# ETHERNET.net
KiCad netlist of a schematic drawn in Altium Designer
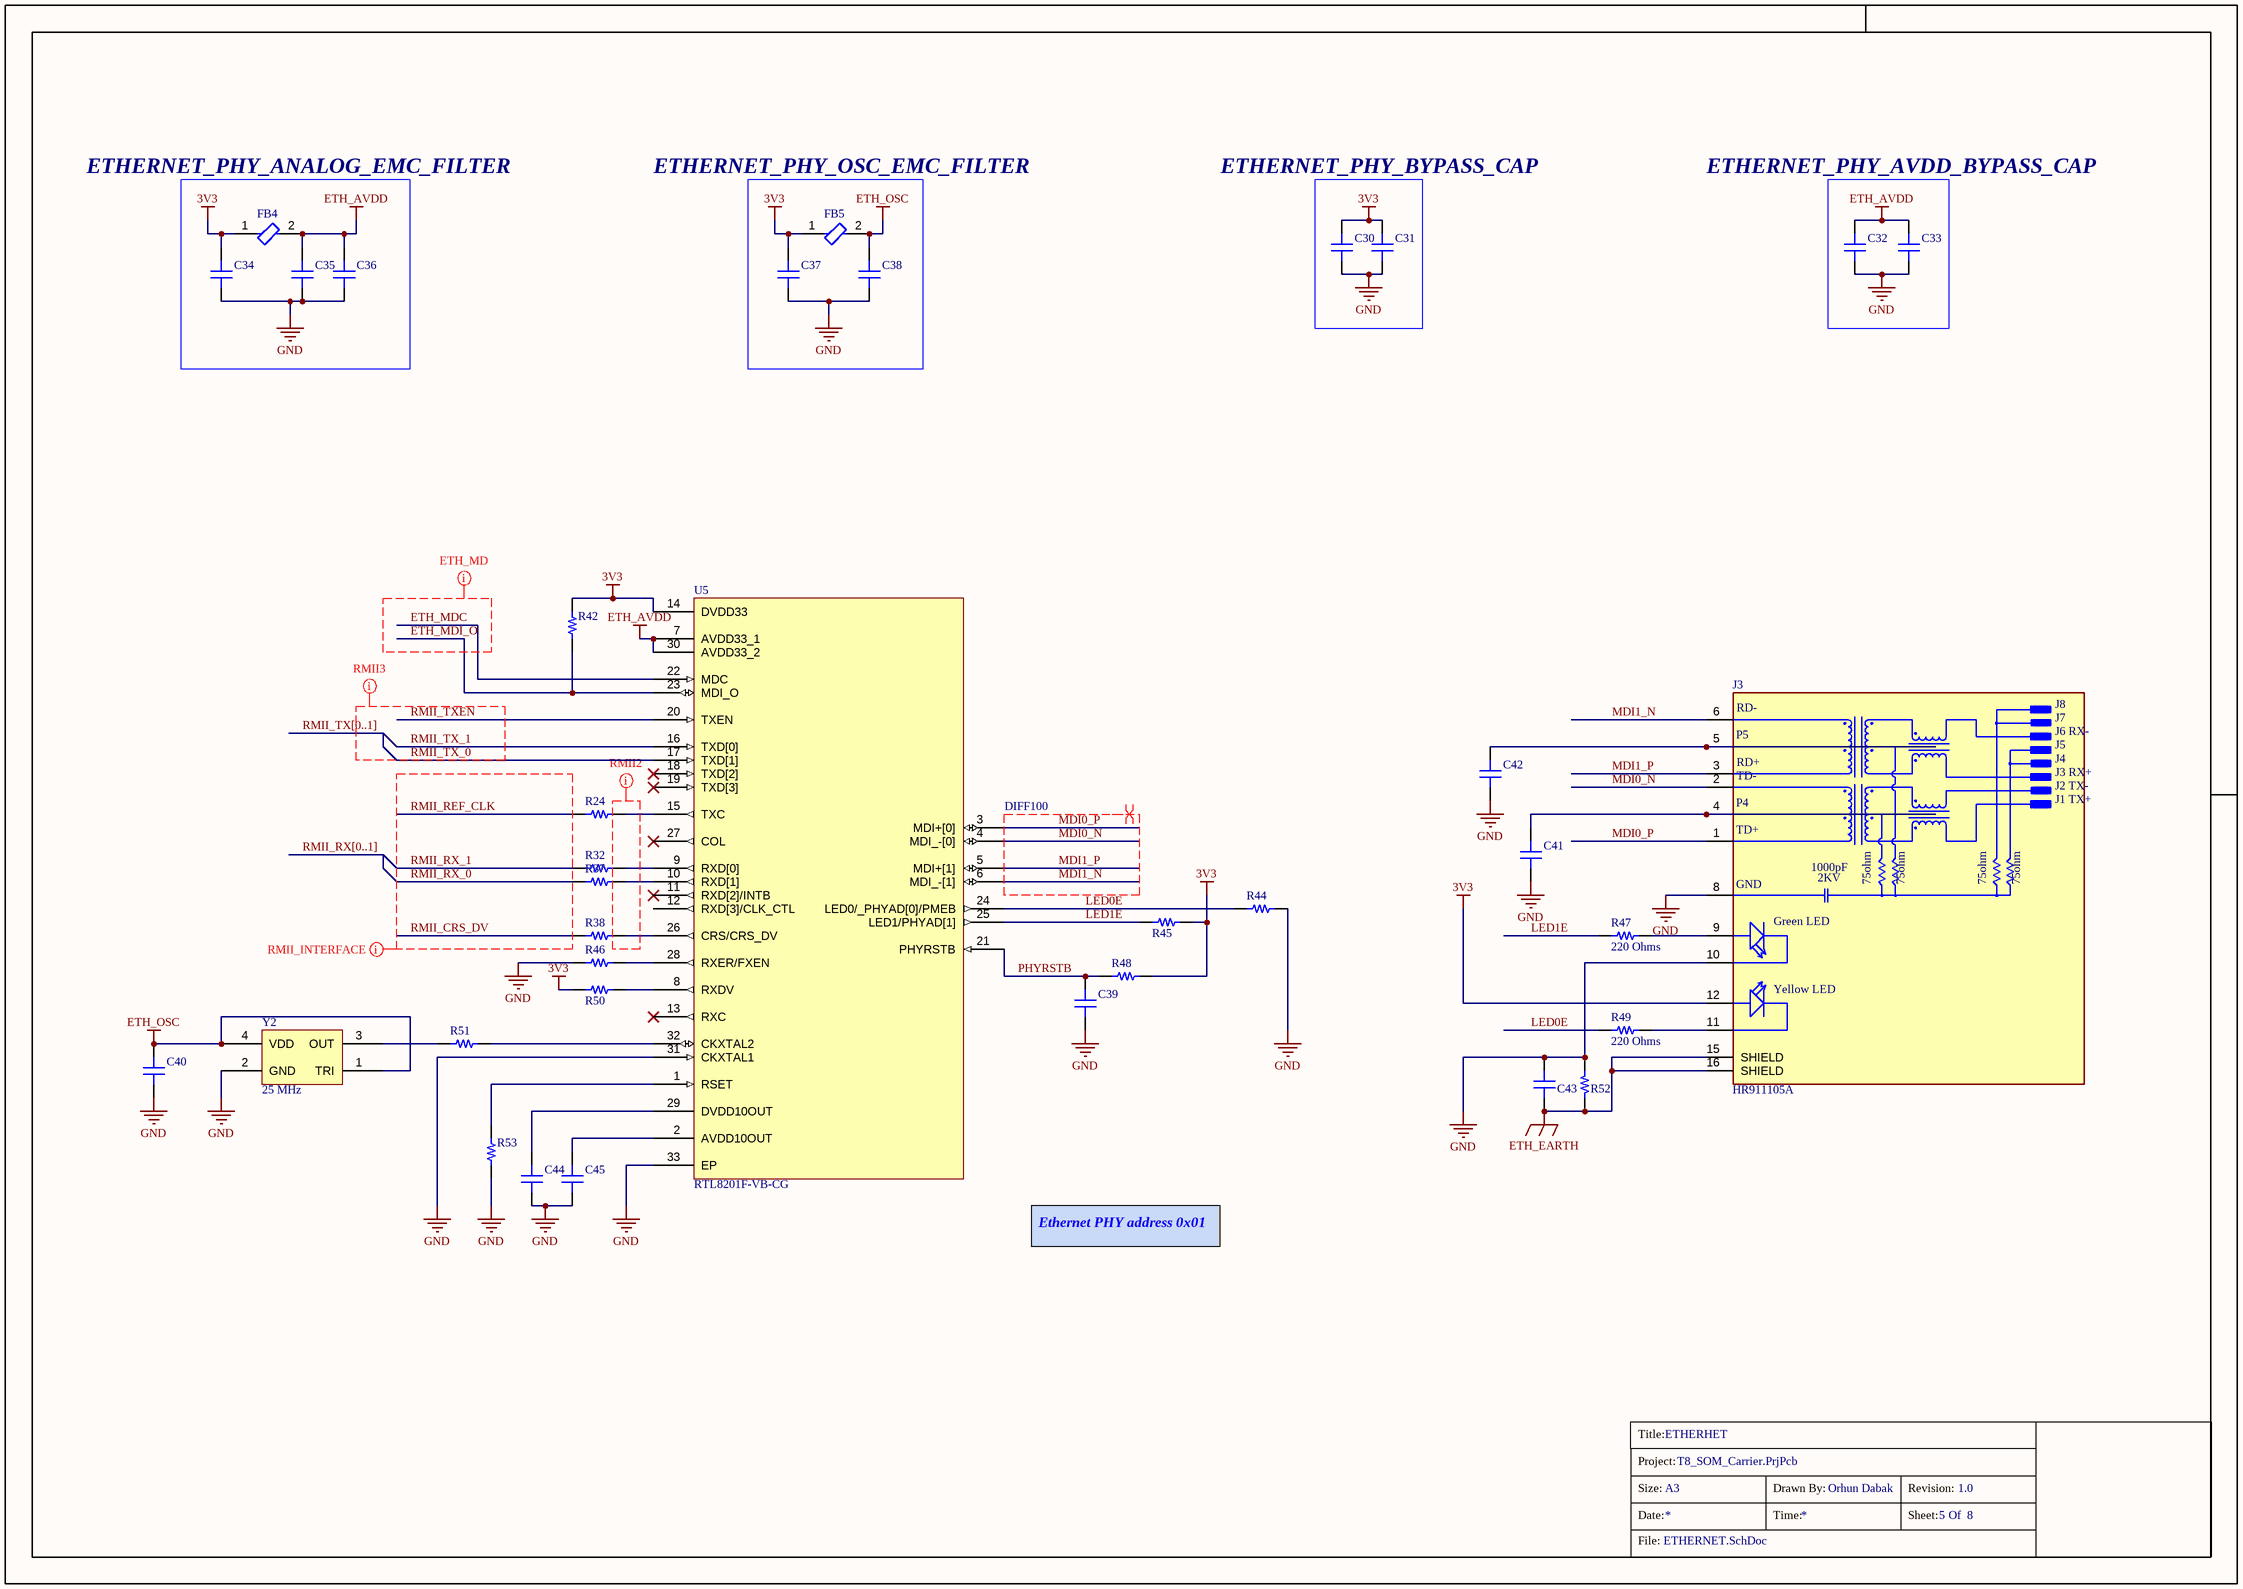
[diagram p0: ETHERNET.SchDoc]

(export (version "E")
  (design (tool "Eeschema 10.0.6"))
  (components
    (comp (ref "C30")
      (value "0.1 µF")
      (footprint "CAP 0402_1005")
      (description "CAP CER 0.1UF 10V X7R 0402")
      (fields (field (name "PART NUMBER") "CC0402KRX7R6BB104") (field (name "MANUFACTURER") "Yageo"))
      (libsource (lib "Celestial Altium Library - altium_library") (part "Capacitor"))
    )
    (comp (ref "C31")
      (value "2.2 µF")
      (footprint "CAP 0402_1005")
      (description "CAP CER 2.2UF 10V X5R 0402")
      (fields (field (name "PART NUMBER") "C0402C225M8PAC7867") (field (name "MANUFACTURER") "KEMET"))
      (libsource (lib "Celestial Altium Library - altium_library") (part "Capacitor"))
    )
    (comp (ref "C32")
      (value "0.1 µF")
      (footprint "CAP 0402_1005")
      (description "CAP CER 0.1UF 10V X7R 0402")
      (fields (field (name "PART NUMBER") "CC0402KRX7R6BB104") (field (name "MANUFACTURER") "Yageo"))
      (libsource (lib "Celestial Altium Library - altium_library") (part "Capacitor"))
    )
    (comp (ref "C33")
      (value "0.1 µF")
      (footprint "CAP 0402_1005")
      (description "CAP CER 0.1UF 10V X7R 0402")
      (fields (field (name "PART NUMBER") "CC0402KRX7R6BB104") (field (name "MANUFACTURER") "Yageo"))
      (libsource (lib "Celestial Altium Library - altium_library") (part "Capacitor"))
    )
    (comp (ref "C34")
      (value "0.1 µF")
      (footprint "CAP 0402_1005")
      (description "CAP CER 0.1UF 10V X7R 0402")
      (fields (field (name "PART NUMBER") "CC0402KRX7R6BB104") (field (name "MANUFACTURER") "Yageo"))
      (libsource (lib "Celestial Altium Library - altium_library") (part "Capacitor"))
    )
    (comp (ref "C35")
      (value "0.1 µF")
      (footprint "CAP 0402_1005")
      (description "CAP CER 0.1UF 10V X7R 0402")
      (fields (field (name "PART NUMBER") "CC0402KRX7R6BB104") (field (name "MANUFACTURER") "Yageo"))
      (libsource (lib "Celestial Altium Library - altium_library") (part "Capacitor"))
    )
    (comp (ref "C36")
      (value "4.7 µF")
      (footprint "CAP 0402_1005")
      (description "CAP CER 4.7UF 10V X5R 0402")
      (fields
        (field (name "PART NUMBER") "CL05A475MP5NRNC")
        (field (name "MANUFACTURER") "Samsung Electro-Mechanics")
      )
      (libsource (lib "Celestial Altium Library - altium_library") (part "Capacitor"))
    )
    (comp (ref "C37")
      (value "4.7 µF")
      (footprint "CAP 0402_1005")
      (description "CAP CER 4.7UF 10V X5R 0402")
      (fields
        (field (name "PART NUMBER") "CL05A475MP5NRNC")
        (field (name "MANUFACTURER") "Samsung Electro-Mechanics")
      )
      (libsource (lib "Celestial Altium Library - altium_library") (part "Capacitor"))
    )
    (comp (ref "C38")
      (value "4.7 µF")
      (footprint "CAP 0402_1005")
      (description "CAP CER 4.7UF 10V X5R 0402")
      (fields
        (field (name "PART NUMBER") "CL05A475MP5NRNC")
        (field (name "MANUFACTURER") "Samsung Electro-Mechanics")
      )
      (libsource (lib "Celestial Altium Library - altium_library") (part "Capacitor"))
    )
    (comp (ref "C39")
      (value "1000pF")
      (footprint "CAP 0402_1005")
      (description "CAP CER 1000PF 10V X7R 0402")
      (fields (field (name "PART NUMBER") "0402ZC102KAT2A") (field (name "MANUFACTURER") "AVX Corporation"))
      (libsource (lib "Celestial Altium Library - altium_library") (part "Capacitor"))
    )
    (comp (ref "C40")
      (value "0.1 µF")
      (footprint "CAP 0402_1005")
      (description "CAP CER 0.1UF 10V X7R 0402")
      (fields (field (name "PART NUMBER") "CC0402KRX7R6BB104") (field (name "MANUFACTURER") "Yageo"))
      (libsource (lib "Celestial Altium Library - altium_library") (part "Capacitor"))
    )
    (comp (ref "C41")
      (value "10000 pF")
      (footprint "CAP 0402_1005")
      (description "CAP CER 0402 10NF 50V X7R 10%")
      (fields (field (name "PART NUMBER") "C0402C103K5RECAUTO") (field (name "MANUFACTURER") "KEMET"))
      (libsource (lib "Celestial Altium Library - altium_library") (part "Capacitor"))
    )
    (comp (ref "C42")
      (value "10000 pF")
      (footprint "CAP 0402_1005")
      (description "CAP CER 0402 10NF 50V X7R 10%")
      (fields (field (name "PART NUMBER") "C0402C103K5RECAUTO") (field (name "MANUFACTURER") "KEMET"))
      (libsource (lib "Celestial Altium Library - altium_library") (part "Capacitor"))
    )
    (comp (ref "C43")
      (value "4700 pF")
      (footprint "CAP 0402_1005")
      (description "CAP CER 4700PF 100V X7R 0402")
      (fields
        (field (name "PART NUMBER") "GRM155R72A472KA01D")
        (field (name "MANUFACTURER") "Murata Electronics")
      )
      (libsource (lib "Celestial Altium Library - altium_library") (part "Capacitor"))
    )
    (comp (ref "C44")
      (value "0.1 µF")
      (footprint "CAP 0402_1005")
      (description "CAP CER 0.1UF 10V X7R 0402")
      (fields (field (name "PART NUMBER") "CC0402KRX7R6BB104") (field (name "MANUFACTURER") "Yageo"))
      (libsource (lib "Celestial Altium Library - altium_library") (part "Capacitor"))
    )
    (comp (ref "C45")
      (value "0.1 µF")
      (footprint "CAP 0402_1005")
      (description "CAP CER 0.1UF 10V X7R 0402")
      (fields (field (name "PART NUMBER") "CC0402KRX7R6BB104") (field (name "MANUFACTURER") "Yageo"))
      (libsource (lib "Celestial Altium Library - altium_library") (part "Capacitor"))
    )
    (comp (ref "FB4")
      (value "BLM15AX601SN1D")
      (footprint "FP-BLM15-0_05-IPC_B")
      (description "Chip Ferrite Bead, 0402, 600Ω @ 100MHz, 0.34Ω, 25%, 500mA")
      (fields (field (name "TOLERANCE") "25%"))
      (libsource (lib "Altium Content Vault") (part "5f30dd21d616792df468990f7003faa"))
    )
    (comp (ref "FB5")
      (value "BLM15AX601SN1D")
      (footprint "FP-BLM15-0_05-IPC_B")
      (description "Chip Ferrite Bead, 0402, 600Ω @ 100MHz, 0.34Ω, 25%, 500mA")
      (fields (field (name "TOLERANCE") "25%"))
      (libsource (lib "Altium Content Vault") (part "5f30dd21d616792df468990f7003faa"))
    )
    (comp (ref "J3")
      (value "HR911105A")
      (footprint "HANRUN_HR911105A:HANRUN_HR911105A")
      (description "DIP RJ45 Connector;")
      (libsource (lib "HR911105A") (part "HR911105A"))
    )
    (comp (ref "R24")
      (value "22 Ohms")
      (footprint "RES 0201_0603")
      (description "RES SMD 22 OHM 1% 1/20W 0201")
      (fields
        (field (name "PART NUMBER") "ERJ-1GNF22R0C")
        (field (name "MANUFACTURER") "Panasonic Electronic Components")
      )
      (libsource (lib "Celestial Altium Library - altium_library") (part "Resistor"))
    )
    (comp (ref "R32")
      (value "22 Ohms")
      (footprint "RES 0201_0603")
      (description "RES SMD 22 OHM 1% 1/20W 0201")
      (fields
        (field (name "PART NUMBER") "ERJ-1GNF22R0C")
        (field (name "MANUFACTURER") "Panasonic Electronic Components")
      )
      (libsource (lib "Celestial Altium Library - altium_library") (part "Resistor"))
    )
    (comp (ref "R37")
      (value "22 Ohms")
      (footprint "RES 0201_0603")
      (description "RES SMD 22 OHM 1% 1/20W 0201")
      (fields
        (field (name "PART NUMBER") "ERJ-1GNF22R0C")
        (field (name "MANUFACTURER") "Panasonic Electronic Components")
      )
      (libsource (lib "Celestial Altium Library - altium_library") (part "Resistor"))
    )
    (comp (ref "R38")
      (value "22 Ohms")
      (footprint "RES 0201_0603")
      (description "RES SMD 22 OHM 1% 1/20W 0201")
      (fields
        (field (name "PART NUMBER") "ERJ-1GNF22R0C")
        (field (name "MANUFACTURER") "Panasonic Electronic Components")
      )
      (libsource (lib "Celestial Altium Library - altium_library") (part "Resistor"))
    )
    (comp (ref "R42")
      (value "10 kOhms")
      (footprint "RES 0201_0603")
      (description "RES 10K OHM 1% 1/20W 0201")
      (fields (field (name "PART NUMBER") "RC0201FR-0710KL") (field (name "MANUFACTURER") "Yageo"))
      (libsource (lib "Celestial Altium Library - altium_library") (part "Resistor"))
    )
    (comp (ref "R44")
      (value "4.7 kOhms")
      (footprint "RES 0201_0603")
      (description "RES 4.7K OHM 1% 1/20W 0201")
      (fields (field (name "PART NUMBER") "RC0201FR-074K7L") (field (name "MANUFACTURER") "Yageo"))
      (libsource (lib "Celestial Altium Library - altium_library") (part "Resistor"))
    )
    (comp (ref "R45")
      (value "4.7 kOhms")
      (footprint "RES 0201_0603")
      (description "RES 4.7K OHM 1% 1/20W 0201")
      (fields (field (name "PART NUMBER") "RC0201FR-074K7L") (field (name "MANUFACTURER") "Yageo"))
      (libsource (lib "Celestial Altium Library - altium_library") (part "Resistor"))
    )
    (comp (ref "R46")
      (value "4.7 kOhms")
      (footprint "RES 0201_0603")
      (description "RES 4.7K OHM 1% 1/20W 0201")
      (fields (field (name "PART NUMBER") "RC0201FR-074K7L") (field (name "MANUFACTURER") "Yageo"))
      (libsource (lib "Celestial Altium Library - altium_library") (part "Resistor"))
    )
    (comp (ref "R47")
      (value "220 Ohms")
      (footprint "RES 0402_1005")
      (description "RES 220 OHM 1% 1/16W 0402")
      (fields (field (name "PART NUMBER") "RC0402FR-07220RL") (field (name "MANUFACTURER") "Yageo"))
      (libsource (lib "Celestial Altium Library - altium_library") (part "Resistor"))
    )
    (comp (ref "R48")
      (value "4.7 kOhms")
      (footprint "RES 0201_0603")
      (description "RES 4.7K OHM 1% 1/20W 0201")
      (fields (field (name "PART NUMBER") "RC0201FR-074K7L") (field (name "MANUFACTURER") "Yageo"))
      (libsource (lib "Celestial Altium Library - altium_library") (part "Resistor"))
    )
    (comp (ref "R49")
      (value "220 Ohms")
      (footprint "RES 0402_1005")
      (description "RES 220 OHM 1% 1/16W 0402")
      (fields (field (name "PART NUMBER") "RC0402FR-07220RL") (field (name "MANUFACTURER") "Yageo"))
      (libsource (lib "Celestial Altium Library - altium_library") (part "Resistor"))
    )
    (comp (ref "R50")
      (value "10 kOhms")
      (footprint "RES 0201_0603")
      (description "RES 10K OHM 1% 1/20W 0201")
      (fields (field (name "PART NUMBER") "RC0201FR-0710KL") (field (name "MANUFACTURER") "Yageo"))
      (libsource (lib "Celestial Altium Library - altium_library") (part "Resistor"))
    )
    (comp (ref "R51")
      (value "22 Ohms")
      (footprint "RES 0402_1005")
      (description "RES 22 OHM 1% 1/16W 0402")
      (fields (field (name "PART NUMBER") "RC0402FR-0722RL") (field (name "MANUFACTURER") "Yageo"))
      (libsource (lib "Celestial Altium Library - altium_library") (part "Resistor"))
    )
    (comp (ref "R52")
      (value "1 MOhms")
      (footprint "RES 0402_1005")
      (description "RES SMD 1M OHM 1% 1/16W 0402")
      (fields (field (name "PART NUMBER") "AC0402FR-071ML") (field (name "MANUFACTURER") "Yageo"))
      (libsource (lib "Celestial Altium Library - altium_library") (part "Resistor"))
    )
    (comp (ref "R53")
      (value "2.49 kOhms")
      (footprint "RES 0201_0603")
      (description "RES 2.49K OHM 1% 1/20W 0201")
      (fields (field (name "PART NUMBER") "RC0201FR-072K49L") (field (name "MANUFACTURER") "Yageo"))
      (libsource (lib "Celestial Altium Library - altium_library") (part "Resistor"))
    )
    (comp (ref "U5")
      (value "RTL8201F-VB-CG")
      (footprint "QFN50P500X500X100_HS-33N")
      (fields (field (name "MANUFACTURER") "Realtek Semicon"))
      (libsource (lib "T8_devkit_PCB") (part "RTL8201F-VB-CG"))
    )
    (comp (ref "Y2")
      (value "25 MHz")
      (footprint "ABRACON ASE")
      (description "XTAL OSC XO 25.0000MHZ CMOS SMD")
      (fields (field (name "PART NUMBER") "ASE-25.000MHZ-ET") (field (name "MANUFACTURER") "Abracon LLC"))
      (libsource (lib "Celestial Altium Library - altium_library") (part "Abracon XO ASE"))
    )
  )
  (nets
    (net (code "5") (name "/ETH_MDC") (class "Default")
      (node (ref "U5") (pin "22") (pinfunction "MDC_22") (pintype "input"))
    )
    (net (code "6") (name "/ETH_MDI_O") (class "Default")
      (node (ref "R42") (pin "1") (pinfunction "1_1") (pintype "passive"))
      (node (ref "U5") (pin "23") (pinfunction "MDI_O_23") (pintype "bidirectional"))
    )
    (net (code "7") (name "/LED0E") (class "Default")
      (node (ref "R44") (pin "1") (pinfunction "1_1") (pintype "passive"))
      (node (ref "R49") (pin "2") (pinfunction "2_2") (pintype "passive"))
      (node (ref "U5") (pin "24") (pinfunction "LED0/_PHYAD[0]/PMEB_24") (pintype "output"))
    )
    (net (code "8") (name "/LED1E") (class "Default")
      (node (ref "R45") (pin "2") (pinfunction "2_2") (pintype "passive"))
      (node (ref "R47") (pin "2") (pinfunction "2_2") (pintype "passive"))
      (node (ref "U5") (pin "25") (pinfunction "LED1/PHYAD[1]_25") (pintype "output"))
    )
    (net (code "9") (name "/MDI0_N") (class "Default")
      (node (ref "J3") (pin "2") (pinfunction "TD-_2") (pintype "passive"))
      (node (ref "U5") (pin "4") (pinfunction "MDI_-[0]_4") (pintype "bidirectional"))
    )
    (net (code "10") (name "/MDI0_P") (class "Default")
      (node (ref "J3") (pin "1") (pinfunction "TD+_1") (pintype "passive"))
      (node (ref "U5") (pin "3") (pinfunction "MDI+[0]_3") (pintype "bidirectional"))
    )
    (net (code "11") (name "/MDI1_N") (class "Default")
      (node (ref "J3") (pin "6") (pinfunction "RD-_6") (pintype "passive"))
      (node (ref "U5") (pin "6") (pinfunction "MDI_-[1]_6") (pintype "bidirectional"))
    )
    (net (code "12") (name "/MDI1_P") (class "Default")
      (node (ref "J3") (pin "3") (pinfunction "RD+_3") (pintype "passive"))
      (node (ref "U5") (pin "5") (pinfunction "MDI+[1]_5") (pintype "bidirectional"))
    )
    (net (code "13") (name "/PHYRSTB") (class "Default")
      (node (ref "C39") (pin "2") (pinfunction "2_2") (pintype "passive"))
      (node (ref "R48") (pin "1") (pinfunction "1_1") (pintype "passive"))
      (node (ref "U5") (pin "21") (pinfunction "PHYRSTB_21") (pintype "input"))
    )
    (net (code "14") (name "/RMII_CRS_DV") (class "Default")
      (node (ref "R38") (pin "1") (pinfunction "1_1") (pintype "passive"))
    )
    (net (code "15") (name "/RMII_REF_CLK") (class "Default")
      (node (ref "R24") (pin "1") (pinfunction "1_1") (pintype "passive"))
    )
    (net (code "17") (name "/RMII_RX_0") (class "Default")
      (node (ref "R37") (pin "1") (pinfunction "1_1") (pintype "passive"))
    )
    (net (code "18") (name "/RMII_RX_1") (class "Default")
      (node (ref "R32") (pin "1") (pinfunction "1_1") (pintype "passive"))
    )
    (net (code "19") (name "/RMII_TXEN") (class "Default")
      (node (ref "U5") (pin "20") (pinfunction "TXEN_20") (pintype "input"))
    )
    (net (code "21") (name "/RMII_TX_0") (class "Default")
      (node (ref "U5") (pin "17") (pinfunction "TXD[1]_17") (pintype "input"))
    )
    (net (code "22") (name "/RMII_TX_1") (class "Default")
      (node (ref "U5") (pin "16") (pinfunction "TXD[0]_16") (pintype "input"))
    )
    (net (code "23") (name "3V3") (class "Default")
      (node (ref "C30") (pin "2") (pinfunction "2_2") (pintype "passive"))
      (node (ref "C31") (pin "2") (pinfunction "2_2") (pintype "passive"))
      (node (ref "C34") (pin "2") (pinfunction "2_2") (pintype "passive"))
      (node (ref "C37") (pin "2") (pinfunction "2_2") (pintype "passive"))
      (node (ref "FB4") (pin "1") (pinfunction "1_1") (pintype "passive"))
      (node (ref "FB5") (pin "1") (pinfunction "1_1") (pintype "passive"))
      (node (ref "J3") (pin "12") (pinfunction "YA_12") (pintype "passive"))
      (node (ref "R42") (pin "2") (pinfunction "2_2") (pintype "passive"))
      (node (ref "R45") (pin "1") (pinfunction "1_1") (pintype "passive"))
      (node (ref "R48") (pin "2") (pinfunction "2_2") (pintype "passive"))
      (node (ref "R50") (pin "2") (pinfunction "2_2") (pintype "passive"))
      (node (ref "U5") (pin "14") (pinfunction "DVDD33_14") (pintype "power_in"))
    )
    (net (code "24") (name "ETH_AVDD") (class "Default")
      (node (ref "C32") (pin "2") (pinfunction "2_2") (pintype "passive"))
      (node (ref "C33") (pin "2") (pinfunction "2_2") (pintype "passive"))
      (node (ref "C35") (pin "2") (pinfunction "2_2") (pintype "passive"))
      (node (ref "C36") (pin "2") (pinfunction "2_2") (pintype "passive"))
      (node (ref "FB4") (pin "2") (pinfunction "2_2") (pintype "passive"))
      (node (ref "U5") (pin "30") (pinfunction "AVDD33_2_30") (pintype "power_in"))
      (node (ref "U5") (pin "7") (pinfunction "AVDD33_1_7") (pintype "power_in"))
    )
    (net (code "25") (name "ETH_EARTH") (class "Default")
      (node (ref "C43") (pin "1") (pinfunction "1_1") (pintype "passive"))
      (node (ref "J3") (pin "15") (pinfunction "SHIELD_15") (pintype "passive"))
      (node (ref "J3") (pin "16") (pinfunction "SHIELD_16") (pintype "passive"))
      (node (ref "R52") (pin "1") (pinfunction "1_1") (pintype "passive"))
    )
    (net (code "26") (name "ETH_OSC") (class "Default")
      (node (ref "C38") (pin "2") (pinfunction "2_2") (pintype "passive"))
      (node (ref "C40") (pin "2") (pinfunction "2_2") (pintype "passive"))
      (node (ref "FB5") (pin "2") (pinfunction "2_2") (pintype "passive"))
      (node (ref "Y2") (pin "1") (pinfunction "TRI_1") (pintype "passive"))
      (node (ref "Y2") (pin "4") (pinfunction "VDD_4") (pintype "passive"))
    )
    (net (code "27") (name "GND") (class "Default")
      (node (ref "C30") (pin "1") (pinfunction "1_1") (pintype "passive"))
      (node (ref "C31") (pin "1") (pinfunction "1_1") (pintype "passive"))
      (node (ref "C32") (pin "1") (pinfunction "1_1") (pintype "passive"))
      (node (ref "C33") (pin "1") (pinfunction "1_1") (pintype "passive"))
      (node (ref "C34") (pin "1") (pinfunction "1_1") (pintype "passive"))
      (node (ref "C35") (pin "1") (pinfunction "1_1") (pintype "passive"))
      (node (ref "C36") (pin "1") (pinfunction "1_1") (pintype "passive"))
      (node (ref "C37") (pin "1") (pinfunction "1_1") (pintype "passive"))
      (node (ref "C38") (pin "1") (pinfunction "1_1") (pintype "passive"))
      (node (ref "C39") (pin "1") (pinfunction "1_1") (pintype "passive"))
      (node (ref "C40") (pin "1") (pinfunction "1_1") (pintype "passive"))
      (node (ref "C41") (pin "1") (pinfunction "1_1") (pintype "passive"))
      (node (ref "C42") (pin "1") (pinfunction "1_1") (pintype "passive"))
      (node (ref "C43") (pin "2") (pinfunction "2_2") (pintype "passive"))
      (node (ref "C44") (pin "1") (pinfunction "1_1") (pintype "passive"))
      (node (ref "C45") (pin "1") (pinfunction "1_1") (pintype "passive"))
      (node (ref "J3") (pin "10") (pinfunction "GC_10") (pintype "passive"))
      (node (ref "J3") (pin "8") (pinfunction "GND_8") (pintype "power_in"))
      (node (ref "R44") (pin "2") (pinfunction "2_2") (pintype "passive"))
      (node (ref "R46") (pin "1") (pinfunction "1_1") (pintype "passive"))
      (node (ref "R52") (pin "2") (pinfunction "2_2") (pintype "passive"))
      (node (ref "R53") (pin "1") (pinfunction "1_1") (pintype "passive"))
      (node (ref "U5") (pin "31") (pinfunction "CKXTAL1_31") (pintype "input"))
      (node (ref "U5") (pin "33") (pinfunction "EP_33") (pintype "power_in"))
      (node (ref "Y2") (pin "2") (pinfunction "GND_2") (pintype "passive"))
    )
    (net (code "28") (name "Net-(J3-GA)") (class "Default")
      (node (ref "J3") (pin "9") (pinfunction "GA_9") (pintype "passive"))
      (node (ref "R47") (pin "1") (pinfunction "1_1") (pintype "passive"))
    )
    (net (code "29") (name "Net-(J3-P4)") (class "Default")
      (node (ref "C41") (pin "2") (pinfunction "2_2") (pintype "passive"))
      (node (ref "J3") (pin "4") (pinfunction "P4_4") (pintype "passive"))
    )
    (net (code "30") (name "Net-(J3-P5)") (class "Default")
      (node (ref "C42") (pin "2") (pinfunction "2_2") (pintype "passive"))
      (node (ref "J3") (pin "5") (pinfunction "P5_5") (pintype "passive"))
    )
    (net (code "31") (name "Net-(J3-YC)") (class "Default")
      (node (ref "J3") (pin "11") (pinfunction "YC_11") (pintype "passive"))
      (node (ref "R49") (pin "1") (pinfunction "1_1") (pintype "passive"))
    )
    (net (code "32") (name "Net-(U5-AVDD10OUT)") (class "Default")
      (node (ref "C45") (pin "2") (pinfunction "2_2") (pintype "passive"))
      (node (ref "U5") (pin "2") (pinfunction "AVDD10OUT_2") (pintype "power_in"))
    )
    (net (code "33") (name "Net-(U5-CKXTAL2)") (class "Default")
      (node (ref "R51") (pin "2") (pinfunction "2_2") (pintype "passive"))
      (node (ref "U5") (pin "32") (pinfunction "CKXTAL2_32") (pintype "bidirectional"))
    )
    (net (code "34") (name "Net-(U5-CRS{slash}CRS_DV)") (class "Default")
      (node (ref "R38") (pin "2") (pinfunction "2_2") (pintype "passive"))
      (node (ref "U5") (pin "26") (pinfunction "CRS/CRS_DV_26") (pintype "output"))
    )
    (net (code "35") (name "Net-(U5-DVDD10OUT)") (class "Default")
      (node (ref "C44") (pin "2") (pinfunction "2_2") (pintype "passive"))
      (node (ref "U5") (pin "29") (pinfunction "DVDD10OUT_29") (pintype "power_in"))
    )
    (net (code "36") (name "Net-(U5-RSET)") (class "Default")
      (node (ref "R53") (pin "2") (pinfunction "2_2") (pintype "passive"))
      (node (ref "U5") (pin "1") (pinfunction "RSET_1") (pintype "input"))
    )
    (net (code "37") (name "Net-(U5-RXDV)") (class "Default")
      (node (ref "R50") (pin "1") (pinfunction "1_1") (pintype "passive"))
      (node (ref "U5") (pin "8") (pinfunction "RXDV_8") (pintype "output"))
    )
    (net (code "38") (name "Net-(U5-RXD[0])") (class "Default")
      (node (ref "R32") (pin "2") (pinfunction "2_2") (pintype "passive"))
      (node (ref "U5") (pin "9") (pinfunction "RXD[0]_9") (pintype "output"))
    )
    (net (code "39") (name "Net-(U5-RXD[1])") (class "Default")
      (node (ref "R37") (pin "2") (pinfunction "2_2") (pintype "passive"))
      (node (ref "U5") (pin "10") (pinfunction "RXD[1]_10") (pintype "output"))
    )
    (net (code "40") (name "Net-(U5-RXER{slash}FXEN)") (class "Default")
      (node (ref "R46") (pin "2") (pinfunction "2_2") (pintype "passive"))
      (node (ref "U5") (pin "28") (pinfunction "RXER/FXEN_28") (pintype "output"))
    )
    (net (code "41") (name "Net-(U5-TXC)") (class "Default")
      (node (ref "R24") (pin "2") (pinfunction "2_2") (pintype "passive"))
      (node (ref "U5") (pin "15") (pinfunction "TXC_15") (pintype "output"))
    )
    (net (code "42") (name "Net-(Y2-OUT)") (class "Default")
      (node (ref "R51") (pin "1") (pinfunction "1_1") (pintype "passive"))
      (node (ref "Y2") (pin "3") (pinfunction "OUT_3") (pintype "passive"))
    )
    (net (code "43") (name "unconnected-(U5-COL-Pad27)") (class "Default")
      (node (ref "U5") (pin "27") (pinfunction "COL_27") (pintype "output+no_connect"))
    )
    (net (code "44") (name "unconnected-(U5-RXC-Pad13)") (class "Default")
      (node (ref "U5") (pin "13") (pinfunction "RXC_13") (pintype "output+no_connect"))
    )
    (net (code "45") (name "unconnected-(U5-RXD[2]{slash}INTB-Pad11)") (class "Default")
      (node (ref "U5") (pin "11") (pinfunction "RXD[2]/INTB_11") (pintype "output+no_connect"))
    )
    (net (code "46") (name "unconnected-(U5-RXD[3]{slash}CLK_CTL-Pad12)") (class "Default")
      (node (ref "U5") (pin "12") (pinfunction "RXD[3]/CLK_CTL_12") (pintype "output"))
    )
    (net (code "47") (name "unconnected-(U5-TXD[2]-Pad18)") (class "Default")
      (node (ref "U5") (pin "18") (pinfunction "TXD[2]_18") (pintype "input+no_connect"))
    )
    (net (code "48") (name "unconnected-(U5-TXD[3]-Pad19)") (class "Default")
      (node (ref "U5") (pin "19") (pinfunction "TXD[3]_19") (pintype "input+no_connect"))
    )
  )
)
